# Power_Supply.net
KiCad netlist of a schematic drawn in Altium Designer
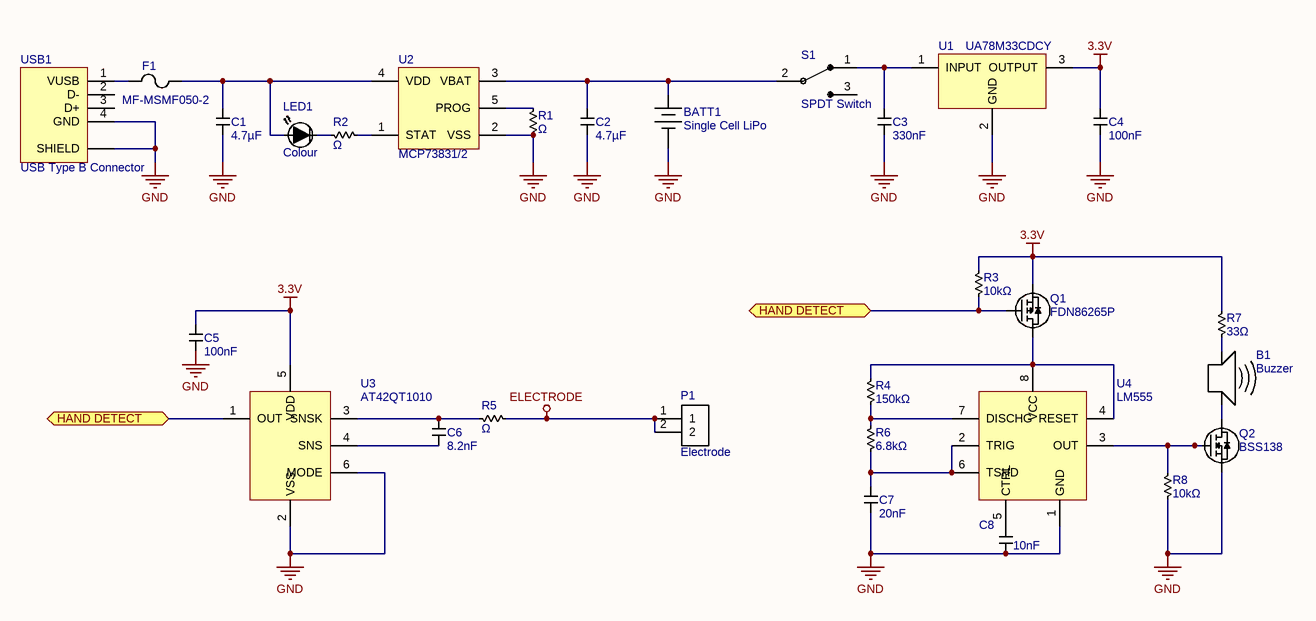
[diagram p0: Power Supply.SchDoc]

(export (version "E")
  (design (tool "Eeschema 10.0.6"))
  (components
    (comp (ref "B1")
      (value "Buzzer")
      (footprint "RS-PRO 535-8449")
      (description "Piezo Buzzer External Drive")
      (libsource (lib "Rigby Electronics Schematic Library") (part "Buzzer"))
    )
    (comp (ref "BATT1")
      (value "Single Cell LiPo")
      (footprint "S2B-XH-A(LF)(SN)")
      (description "Battery")
      (libsource (lib "Rigby Electronics Schematic Library") (part "Battery"))
    )
    (comp (ref "C1")
      (value "4.7µF")
      (footprint "Rigby Electronics Footprint Library:0805")
      (description "Capacitor")
      (libsource (lib "Rigby Electronics Schematic Library") (part "Capacitor"))
    )
    (comp (ref "C2")
      (value "4.7µF")
      (footprint "Rigby Electronics Footprint Library:0805")
      (description "Capacitor")
      (libsource (lib "Rigby Electronics Schematic Library") (part "Capacitor"))
    )
    (comp (ref "C3")
      (value "330nF")
      (footprint "Rigby Electronics Footprint Library:0603")
      (description "Capacitor")
      (libsource (lib "Rigby Electronics Schematic Library") (part "Capacitor"))
    )
    (comp (ref "C4")
      (value "100nF")
      (footprint "Rigby Electronics Footprint Library:0603")
      (description "Capacitor")
      (libsource (lib "Rigby Electronics Schematic Library") (part "Capacitor"))
    )
    (comp (ref "C5")
      (value "100nF")
      (footprint "Rigby Electronics Footprint Library:0603")
      (description "Capacitor")
      (libsource (lib "Rigby Electronics Schematic Library") (part "Capacitor"))
    )
    (comp (ref "C6")
      (value "8.2nF")
      (footprint "Rigby Electronics Footprint Library:0603")
      (description "Capacitor")
      (libsource (lib "Rigby Electronics Schematic Library") (part "Capacitor"))
    )
    (comp (ref "C7")
      (value "20nF")
      (footprint "Rigby Electronics Footprint Library:0603")
      (description "Capacitor")
      (libsource (lib "Rigby Electronics Schematic Library") (part "Capacitor"))
    )
    (comp (ref "C8")
      (value "10nF")
      (footprint "Rigby Electronics Footprint Library:0603")
      (description "Capacitor")
      (libsource (lib "Rigby Electronics Schematic Library") (part "Capacitor"))
    )
    (comp (ref "F1")
      (value "MF-MSMF050-2")
      (footprint "MF-MSMF050-2")
      (description "Resettable Fuse 0.5A 15V")
      (libsource (lib "Rigby Electronics Library") (part "MF-MSMF050-2"))
    )
    (comp (ref "LED1")
      (value "Colour")
      (footprint "0603LED")
      (description "Light Emitting Diode")
      (libsource (lib "Rigby Electronics Library") (part "LED"))
    )
    (comp (ref "P1")
      (value "Electrode")
      (footprint "S2B-XH-A(LF)(SN)")
      (description "2 Pin Header")
      (libsource (lib "Rigby Electronics Schematic Library") (part "Header 2"))
    )
    (comp (ref "Q1")
      (value "FDN86265P")
      (footprint "FDN86265P")
      (description "P-Channel Logic Level MOSFET")
      (libsource (lib "Rigby Electronics Schematic Library") (part "FDN86265P"))
    )
    (comp (ref "Q2")
      (value "BSS138")
      (footprint "BSS138")
      (description "N-Channel Logic Level MOSFET")
      (libsource (lib "Rigby Electronics Schematic Library") (part "BSS138"))
    )
    (comp (ref "R1")
      (value "Ω")
      (footprint "0603")
      (description "Standard Resistor")
      (libsource (lib "") (part "Resistor_1"))
    )
    (comp (ref "R2")
      (value "Ω")
      (footprint "0603")
      (description "Standard Resistor")
      (libsource (lib "Rigby Electronics Library") (part "Resistor"))
    )
    (comp (ref "R3")
      (value "10kΩ")
      (footprint "Rigby Electronics Footprint Library:0603")
      (description "Standard Resistor")
      (libsource (lib "Rigby Electronics Schematic Library") (part "Resistor"))
    )
    (comp (ref "R4")
      (value "150kΩ")
      (footprint "Rigby Electronics Footprint Library:0603")
      (description "Standard Resistor")
      (libsource (lib "Rigby Electronics Schematic Library") (part "Resistor"))
    )
    (comp (ref "R5")
      (value "Ω")
      (footprint "Rigby Electronics Footprint Library:0603")
      (description "Standard Resistor")
      (libsource (lib "Rigby Electronics Schematic Library") (part "Resistor"))
    )
    (comp (ref "R6")
      (value "6.8kΩ")
      (footprint "Rigby Electronics Footprint Library:0603")
      (description "Standard Resistor")
      (libsource (lib "Rigby Electronics Schematic Library") (part "Resistor"))
    )
    (comp (ref "R7")
      (value "33Ω")
      (footprint "Rigby Electronics Footprint Library:0603")
      (description "Standard Resistor")
      (libsource (lib "Rigby Electronics Schematic Library") (part "Resistor"))
    )
    (comp (ref "R8")
      (value "10kΩ")
      (footprint "Rigby Electronics Footprint Library:0603")
      (description "Standard Resistor")
      (libsource (lib "Rigby Electronics Schematic Library") (part "Resistor"))
    )
    (comp (ref "S1")
      (value "SPDT Switch")
      (footprint "MFP120-R")
      (libsource (lib "Rigby Electronics Schematic Library") (part "SPDT Switch"))
    )
    (comp (ref "U1")
      (value "UA78M33CDCY")
      (footprint "UA78M33CDCY")
      (description "Linear Voltage Regulator 3.3V 500mA 25V Input")
      (libsource (lib "Rigby Electronics Library") (part "UA78M33CDCY"))
    )
    (comp (ref "U2")
      (value "MCP73831/2")
      (footprint "MCP73831")
      (description "Li-Ion Charge Management Controller")
      (libsource (lib "Rigby Electronics Schematic Library") (part "MCP73831/2"))
    )
    (comp (ref "U3")
      (value "AT42QT1010")
      (footprint "AT42QT1010")
      (description "Digital Burst Mode Charge Transfer Sensor")
      (libsource (lib "Rigby Electronics Schematic Library") (part "AT42QT1010"))
    )
    (comp (ref "U4")
      (value "LM555")
      (footprint "LM555")
      (description "555 Timer IC")
      (libsource (lib "Rigby Electronics Schematic Library") (part "LM555"))
    )
    (comp (ref "USB1")
      (value "USB Type B Connector")
      (footprint "Amphenol FCI 10103594-0001LF")
      (description "USB Type B Female Connector Right Angle Through Hole")
      (libsource (lib "Rigby Electronics Schematic Library") (part "USB Type B Female Connector"))
    )
  )
  (nets
    (net (code "1") (name "/HAND DETECT") (class "Default")
      (node (ref "Q1") (pin "G") (pinfunction "G_G") (pintype "passive"))
      (node (ref "R3") (pin "1") (pinfunction "1_1") (pintype "passive"))
      (node (ref "U3") (pin "1") (pinfunction "OUT_1") (pintype "passive"))
    )
    (net (code "2") (name "3.3V") (class "Default")
      (node (ref "C4") (pin "1") (pinfunction "1_1") (pintype "passive"))
      (node (ref "C5") (pin "1") (pinfunction "1_1") (pintype "passive"))
      (node (ref "Q1") (pin "S") (pinfunction "S_S") (pintype "passive"))
      (node (ref "R3") (pin "2") (pinfunction "2_2") (pintype "passive"))
      (node (ref "R7") (pin "2") (pinfunction "2_2") (pintype "passive"))
      (node (ref "U1") (pin "3") (pinfunction "OUTPUT_3") (pintype "passive"))
      (node (ref "U3") (pin "5") (pinfunction "VDD_5") (pintype "passive"))
    )
    (net (code "3") (name "ELECTRODE") (class "Default")
      (node (ref "P1") (pin "1") (pinfunction "1_1") (pintype "passive"))
      (node (ref "P1") (pin "2") (pinfunction "2_2") (pintype "passive"))
      (node (ref "R5") (pin "2") (pinfunction "2_2") (pintype "passive"))
    )
    (net (code "4") (name "GND") (class "Default")
      (node (ref "BATT1") (pin "2") (pinfunction "2_2") (pintype "passive"))
      (node (ref "C1") (pin "2") (pinfunction "2_2") (pintype "passive"))
      (node (ref "C2") (pin "2") (pinfunction "2_2") (pintype "passive"))
      (node (ref "C3") (pin "2") (pinfunction "2_2") (pintype "passive"))
      (node (ref "C4") (pin "2") (pinfunction "2_2") (pintype "passive"))
      (node (ref "C5") (pin "2") (pinfunction "2_2") (pintype "passive"))
      (node (ref "C7") (pin "2") (pinfunction "2_2") (pintype "passive"))
      (node (ref "C8") (pin "2") (pinfunction "2_2") (pintype "passive"))
      (node (ref "Q2") (pin "S") (pinfunction "S_S") (pintype "passive"))
      (node (ref "R1") (pin "2") (pinfunction "2_2") (pintype "passive"))
      (node (ref "R8") (pin "1") (pinfunction "1_1") (pintype "passive"))
      (node (ref "U1") (pin "2") (pinfunction "GND_2") (pintype "passive"))
      (node (ref "U2") (pin "2") (pinfunction "VSS_2") (pintype "passive"))
      (node (ref "U3") (pin "2") (pinfunction "VSS_2") (pintype "passive"))
      (node (ref "U3") (pin "6") (pinfunction "MODE_6") (pintype "passive"))
      (node (ref "U4") (pin "1") (pinfunction "GND_1") (pintype "passive"))
      (node (ref "USB1") (pin "4") (pinfunction "GND_4") (pintype "passive"))
      (node (ref "USB1") (pin "SHIELD") (pinfunction "SHIELD_SHIELD") (pintype "passive"))
    )
    (net (code "5") (name "Net-(B1-Pad1)") (class "Default")
      (node (ref "B1") (pin "1") (pinfunction "1_1") (pintype "passive"))
      (node (ref "R7") (pin "1") (pinfunction "1_1") (pintype "passive"))
    )
    (net (code "6") (name "Net-(B1-Pad2)") (class "Default")
      (node (ref "B1") (pin "2") (pinfunction "2_2") (pintype "passive"))
      (node (ref "Q2") (pin "D") (pinfunction "D_D") (pintype "passive"))
    )
    (net (code "7") (name "Net-(LED1-Pad2)") (class "Default")
      (node (ref "LED1") (pin "2") (pinfunction "2_2") (pintype "passive"))
      (node (ref "R2") (pin "1") (pinfunction "1_1") (pintype "passive"))
    )
    (net (code "8") (name "Net-(U1-INPUT)") (class "Default")
      (node (ref "C3") (pin "1") (pinfunction "1_1") (pintype "passive"))
      (node (ref "S1") (pin "1") (pinfunction "1_1") (pintype "passive"))
      (node (ref "U1") (pin "1") (pinfunction "INPUT_1") (pintype "passive"))
    )
    (net (code "9") (name "Net-(U2-PROG)") (class "Default")
      (node (ref "R1") (pin "1") (pinfunction "1_1") (pintype "passive"))
      (node (ref "U2") (pin "5") (pinfunction "PROG_5") (pintype "passive"))
    )
    (net (code "10") (name "Net-(U2-STAT)") (class "Default")
      (node (ref "R2") (pin "2") (pinfunction "2_2") (pintype "passive"))
      (node (ref "U2") (pin "1") (pinfunction "STAT_1") (pintype "passive"))
    )
    (net (code "11") (name "Net-(U2-VBAT)") (class "Default")
      (node (ref "BATT1") (pin "1") (pinfunction "1_1") (pintype "passive"))
      (node (ref "C2") (pin "1") (pinfunction "1_1") (pintype "passive"))
      (node (ref "S1") (pin "2") (pinfunction "2_2") (pintype "passive"))
      (node (ref "U2") (pin "3") (pinfunction "VBAT_3") (pintype "passive"))
    )
    (net (code "12") (name "Net-(U2-VDD)") (class "Default")
      (node (ref "C1") (pin "1") (pinfunction "1_1") (pintype "passive"))
      (node (ref "F1") (pin "2") (pinfunction "2_2") (pintype "passive"))
      (node (ref "LED1") (pin "1") (pinfunction "1_1") (pintype "passive"))
      (node (ref "U2") (pin "4") (pinfunction "VDD_4") (pintype "passive"))
    )
    (net (code "13") (name "Net-(U3-SNS)") (class "Default")
      (node (ref "C6") (pin "2") (pinfunction "2_2") (pintype "passive"))
      (node (ref "U3") (pin "4") (pinfunction "SNS_4") (pintype "passive"))
    )
    (net (code "14") (name "Net-(U3-SNSK)") (class "Default")
      (node (ref "C6") (pin "1") (pinfunction "1_1") (pintype "passive"))
      (node (ref "R5") (pin "1") (pinfunction "1_1") (pintype "passive"))
      (node (ref "U3") (pin "3") (pinfunction "SNSK_3") (pintype "passive"))
    )
    (net (code "15") (name "Net-(U4-CTRL)") (class "Default")
      (node (ref "C8") (pin "1") (pinfunction "1_1") (pintype "passive"))
      (node (ref "U4") (pin "5") (pinfunction "CTRL_5") (pintype "passive"))
    )
    (net (code "16") (name "Net-(U4-DISCHG)") (class "Default")
      (node (ref "R4") (pin "1") (pinfunction "1_1") (pintype "passive"))
      (node (ref "R6") (pin "2") (pinfunction "2_2") (pintype "passive"))
      (node (ref "U4") (pin "7") (pinfunction "DISCHG_7") (pintype "passive"))
    )
    (net (code "17") (name "Net-(U4-OUT)") (class "Default")
      (node (ref "Q2") (pin "G") (pinfunction "G_G") (pintype "passive"))
      (node (ref "R8") (pin "2") (pinfunction "2_2") (pintype "passive"))
      (node (ref "U4") (pin "3") (pinfunction "OUT_3") (pintype "passive"))
    )
    (net (code "18") (name "Net-(U4-RESET)") (class "Default")
      (node (ref "Q1") (pin "D") (pinfunction "D_D") (pintype "passive"))
      (node (ref "R4") (pin "2") (pinfunction "2_2") (pintype "passive"))
      (node (ref "U4") (pin "4") (pinfunction "RESET_4") (pintype "passive"))
      (node (ref "U4") (pin "8") (pinfunction "VCC_8") (pintype "passive"))
    )
    (net (code "19") (name "Net-(U4-TRIG)") (class "Default")
      (node (ref "C7") (pin "1") (pinfunction "1_1") (pintype "passive"))
      (node (ref "R6") (pin "1") (pinfunction "1_1") (pintype "passive"))
      (node (ref "U4") (pin "2") (pinfunction "TRIG_2") (pintype "passive"))
      (node (ref "U4") (pin "6") (pinfunction "TSHD_6") (pintype "passive"))
    )
    (net (code "20") (name "Net-(USB1-VUSB)") (class "Default")
      (node (ref "F1") (pin "1") (pinfunction "1_1") (pintype "passive"))
      (node (ref "USB1") (pin "1") (pinfunction "VUSB_1") (pintype "passive"))
    )
    (net (code "21") (name "unconnected-(S1-Pad3)") (class "Default")
      (node (ref "S1") (pin "3") (pinfunction "3_3") (pintype "passive"))
    )
    (net (code "22") (name "unconnected-(USB1-D+-Pad3)") (class "Default")
      (node (ref "USB1") (pin "3") (pinfunction "D+_3") (pintype "passive"))
    )
    (net (code "23") (name "unconnected-(USB1-D--Pad2)") (class "Default")
      (node (ref "USB1") (pin "2") (pinfunction "D-_2") (pintype "passive"))
    )
  )
)
